# 4069_fuzz_pedal.net
KiCad netlist of a schematic drawn in EAGLE
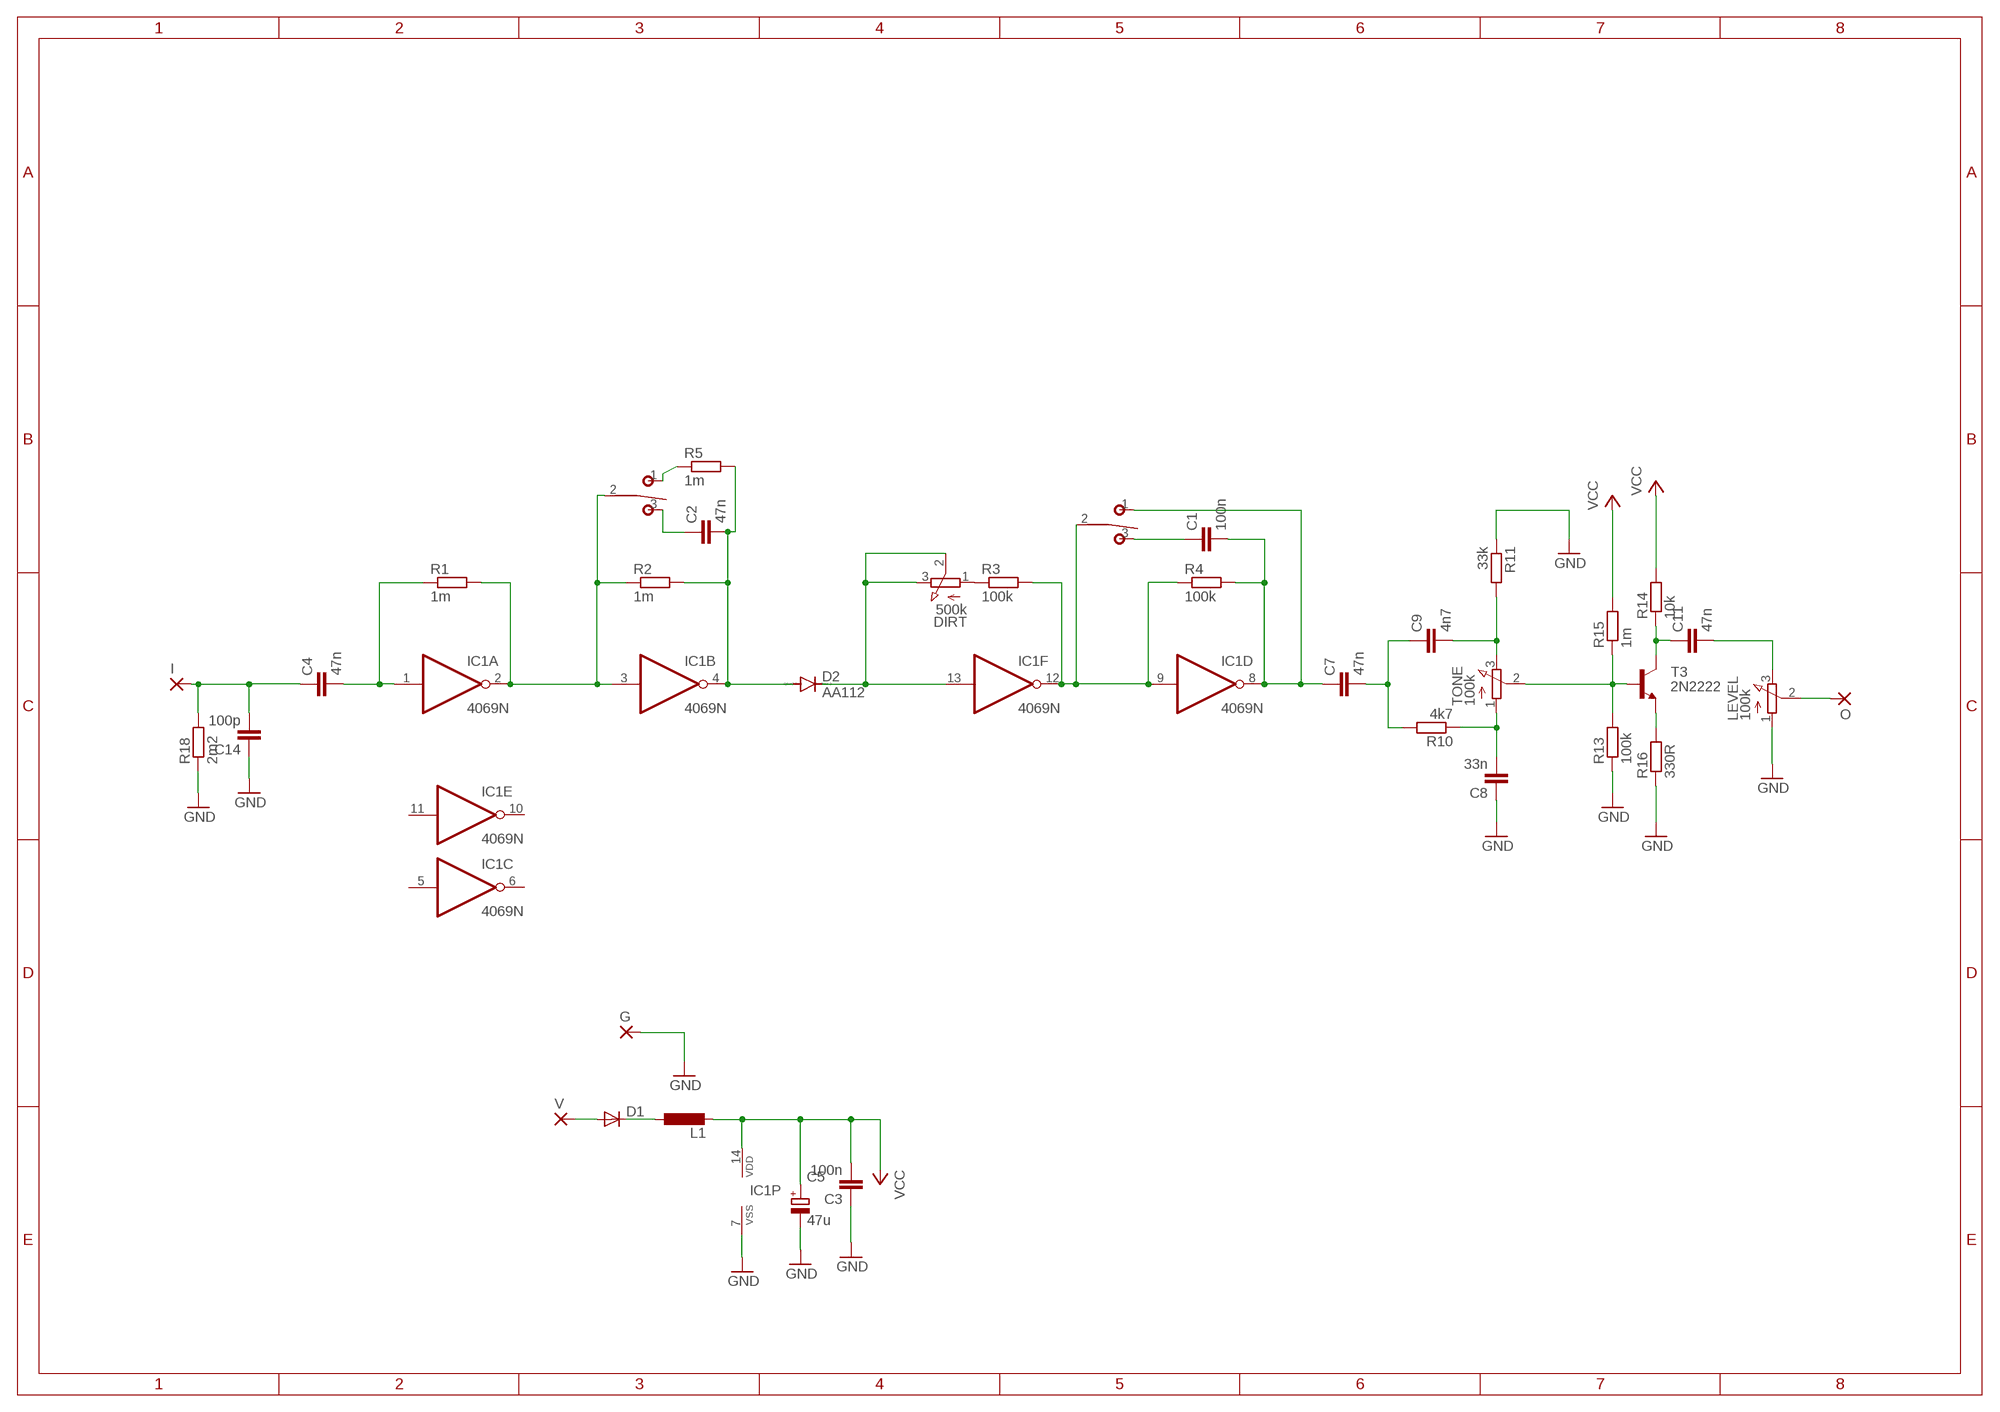
[diagram p0: schematic, sheet 1]

(export (version "E")
  (design (tool "Eeschema 10.0.6"))
  (components
    (comp (ref "C1")
      (value "100n")
      (footprint "eagle-import:C5B2.5")
      (libsource (lib "eagle-import") (part "C5/2.5"))
    )
    (comp (ref "C2")
      (value "47n")
      (footprint "eagle-import:C5B2.5")
      (libsource (lib "eagle-import") (part "C5/2.5"))
    )
    (comp (ref "C3")
      (value "100n")
      (footprint "eagle-import:C5B2.5")
      (libsource (lib "eagle-import") (part "C5/2.5"))
    )
    (comp (ref "C4")
      (value "47n")
      (footprint "eagle-import:C5B2.5")
      (libsource (lib "eagle-import") (part "C5/2.5"))
    )
    (comp (ref "C5")
      (value "47u")
      (footprint "eagle-import:E2-4")
      (libsource (lib "eagle-import") (part "CPOL-EUE2-4"))
    )
    (comp (ref "C7")
      (value "47n")
      (footprint "eagle-import:C5B2.5")
      (libsource (lib "eagle-import") (part "C5/2.5"))
    )
    (comp (ref "C8")
      (value "33n")
      (footprint "eagle-import:C5B2.5")
      (libsource (lib "eagle-import") (part "C5/2.5"))
    )
    (comp (ref "C9")
      (value "4n7")
      (footprint "eagle-import:C5B2.5")
      (libsource (lib "eagle-import") (part "C5/2.5"))
    )
    (comp (ref "C11")
      (value "47n")
      (footprint "eagle-import:C5B2.5")
      (libsource (lib "eagle-import") (part "C5/2.5"))
    )
    (comp (ref "C14")
      (value "100p")
      (footprint "eagle-import:C5B2.5")
      (libsource (lib "eagle-import") (part "C5/2.5"))
    )
    (comp (ref "D1")
      (value "SMALL_DIODEDO35-7")
      (footprint "eagle-import:DO35-7")
      (libsource (lib "eagle-import") (part "SMALL_DIODEDO35-7"))
    )
    (comp (ref "D2")
      (value "AA112")
      (footprint "eagle-import:DO07")
      (libsource (lib "eagle-import") (part "AA112"))
    )
    (comp (ref "DIRT")
      (value "500k")
      (footprint "eagle-import:3RP_1610N")
      (libsource (lib "eagle-import") (part "HEXPOT1"))
    )
    (comp (ref "G")
      (value "2,15/1,0")
      (footprint "eagle-import:2,15_1,0")
      (libsource (lib "eagle-import") (part "2,15/1,0"))
    )
    (comp (ref "I")
      (value "2,15/1,0")
      (footprint "eagle-import:2,15_1,0")
      (libsource (lib "eagle-import") (part "2,15/1,0"))
    )
    (comp (ref "IC1")
      (value "4069N")
      (footprint "eagle-import:DIL14")
      (libsource (lib "eagle-import") (part "4069N"))
    )
    (comp (ref "L1")
      (value "L-EU0204/7")
      (footprint "eagle-import:0204_7")
      (libsource (lib "eagle-import") (part "L-EU0204/7"))
    )
    (comp (ref "LEVEL")
      (value "100k")
      (footprint "eagle-import:3RP_1610N")
      (libsource (lib "eagle-import") (part "HEXPOT1"))
    )
    (comp (ref "O")
      (value "2,15/1,0")
      (footprint "eagle-import:2,15_1,0")
      (libsource (lib "eagle-import") (part "2,15/1,0"))
    )
    (comp (ref "R1")
      (value "1m")
      (footprint "eagle-import:0207_7")
      (libsource (lib "eagle-import") (part "R-EU_0207/7"))
    )
    (comp (ref "R2")
      (value "1m")
      (footprint "eagle-import:0207_7")
      (libsource (lib "eagle-import") (part "R-EU_0207/7"))
    )
    (comp (ref "R3")
      (value "100k")
      (footprint "eagle-import:0207_7")
      (libsource (lib "eagle-import") (part "R-EU_0207/7"))
    )
    (comp (ref "R4")
      (value "100k")
      (footprint "eagle-import:0207_7")
      (libsource (lib "eagle-import") (part "R-EU_0207/7"))
    )
    (comp (ref "R5")
      (value "1m")
      (footprint "eagle-import:0207_7")
      (libsource (lib "eagle-import") (part "R-EU_0207/7"))
    )
    (comp (ref "R10")
      (value "4k7")
      (footprint "eagle-import:0207_7")
      (libsource (lib "eagle-import") (part "R-EU_0207/7"))
    )
    (comp (ref "R11")
      (value "33k")
      (footprint "eagle-import:0207_7")
      (libsource (lib "eagle-import") (part "R-EU_0207/7"))
    )
    (comp (ref "R13")
      (value "100k")
      (footprint "eagle-import:0207_7")
      (libsource (lib "eagle-import") (part "R-EU_0207/7"))
    )
    (comp (ref "R14")
      (value "10k")
      (footprint "eagle-import:0207_7")
      (libsource (lib "eagle-import") (part "R-EU_0207/7"))
    )
    (comp (ref "R15")
      (value "1m")
      (footprint "eagle-import:0207_7")
      (libsource (lib "eagle-import") (part "R-EU_0207/7"))
    )
    (comp (ref "R16")
      (value "330R")
      (footprint "eagle-import:0207_7")
      (libsource (lib "eagle-import") (part "R-EU_0207/7"))
    )
    (comp (ref "R18")
      (value "2m2")
      (footprint "eagle-import:0207_7")
      (libsource (lib "eagle-import") (part "R-EU_0207/7"))
    )
    (comp (ref "T3")
      (value "2N2222")
      (footprint "eagle-import:TO18")
      (libsource (lib "eagle-import") (part "2N2222"))
    )
    (comp (ref "TONE")
      (value "100k")
      (footprint "eagle-import:3RP_1610N")
      (libsource (lib "eagle-import") (part "HEXPOT1"))
    )
    (comp (ref "U$1")
      (value "T-80-T-SPDT-ON-OFF-ON")
      (footprint "eagle-import:M9040P")
      (libsource (lib "eagle-import") (part "T-80-T-SPDT-ON-OFF-ON"))
    )
    (comp (ref "U$2")
      (value "T-80-T-SPDT-ON-OFF-ON")
      (footprint "eagle-import:M9040P")
      (libsource (lib "eagle-import") (part "T-80-T-SPDT-ON-OFF-ON"))
    )
    (comp (ref "V")
      (value "2,15/1,0")
      (footprint "eagle-import:2,15_1,0")
      (libsource (lib "eagle-import") (part "2,15/1,0"))
    )
  )
  (nets
    (net (code "1") (name "GND") (class "Default")
      (node (ref "C14") (pin "1") (pinfunction "1_1") (pintype "passive"))
      (node (ref "C3") (pin "1") (pinfunction "1_1") (pintype "passive"))
      (node (ref "C5") (pin "-") (pinfunction "-_-") (pintype "passive"))
      (node (ref "C8") (pin "1") (pinfunction "1_1") (pintype "passive"))
      (node (ref "G") (pin "1") (pinfunction "P_1") (pintype "passive"))
      (node (ref "IC1") (pin "7") (pinfunction "VSS_7") (pintype "power_in"))
      (node (ref "LEVEL") (pin "1") (pinfunction "A_1") (pintype "passive"))
      (node (ref "R11") (pin "1") (pinfunction "1_1") (pintype "passive"))
      (node (ref "R13") (pin "1") (pinfunction "1_1") (pintype "passive"))
      (node (ref "R16") (pin "1") (pinfunction "1_1") (pintype "passive"))
      (node (ref "R18") (pin "1") (pinfunction "1_1") (pintype "passive"))
    )
    (net (code "2") (name "Net-(C7-Pad2)") (class "Default")
      (node (ref "C7") (pin "2") (pinfunction "2_2") (pintype "passive"))
      (node (ref "C9") (pin "1") (pinfunction "1_1") (pintype "passive"))
      (node (ref "R10") (pin "2") (pinfunction "2_2") (pintype "passive"))
    )
    (net (code "3") (name "Net-(D1-PadC)") (class "Default")
      (node (ref "D1") (pin "C") (pinfunction "C_C") (pintype "passive"))
      (node (ref "L1") (pin "1") (pinfunction "1_1") (pintype "passive"))
    )
    (net (code "4") (name "Net-(DIRT-A)") (class "Default")
      (node (ref "DIRT") (pin "1") (pinfunction "A_1") (pintype "passive"))
      (node (ref "R3") (pin "1") (pinfunction "1_1") (pintype "passive"))
    )
    (net (code "5") (name "Net-(DIRT-E)") (class "Default")
      (node (ref "D2") (pin "C") (pinfunction "C_C") (pintype "passive"))
      (node (ref "DIRT") (pin "2") (pinfunction "S_2") (pintype "passive"))
      (node (ref "DIRT") (pin "3") (pinfunction "E_3") (pintype "passive"))
      (node (ref "IC1") (pin "13") (pinfunction "I_13") (pintype "input"))
    )
    (net (code "6") (name "Net-(I-P)") (class "Default")
      (node (ref "C14") (pin "2") (pinfunction "2_2") (pintype "passive"))
      (node (ref "C4") (pin "1") (pinfunction "1_1") (pintype "passive"))
      (node (ref "I") (pin "1") (pinfunction "P_1") (pintype "passive"))
      (node (ref "R18") (pin "2") (pinfunction "2_2") (pintype "passive"))
    )
    (net (code "7") (name "Net-(IC1A-I)") (class "Default")
      (node (ref "C4") (pin "2") (pinfunction "2_2") (pintype "passive"))
      (node (ref "IC1") (pin "1") (pinfunction "I_1") (pintype "input"))
      (node (ref "R1") (pin "1") (pinfunction "1_1") (pintype "passive"))
    )
    (net (code "8") (name "Net-(IC1A-O)") (class "Default")
      (node (ref "IC1") (pin "2") (pinfunction "O_2") (pintype "output"))
      (node (ref "IC1") (pin "3") (pinfunction "I_3") (pintype "input"))
      (node (ref "R1") (pin "2") (pinfunction "2_2") (pintype "passive"))
      (node (ref "R2") (pin "1") (pinfunction "1_1") (pintype "passive"))
      (node (ref "U$2") (pin "2") (pinfunction "P_2") (pintype "passive"))
    )
    (net (code "9") (name "Net-(IC1B-O)") (class "Default")
      (node (ref "C2") (pin "2") (pinfunction "2_2") (pintype "passive"))
      (node (ref "D2") (pin "A") (pinfunction "A_A") (pintype "passive"))
      (node (ref "IC1") (pin "4") (pinfunction "O_4") (pintype "output"))
      (node (ref "R2") (pin "2") (pinfunction "2_2") (pintype "passive"))
      (node (ref "R5") (pin "2") (pinfunction "2_2") (pintype "passive"))
    )
    (net (code "10") (name "Net-(IC1D-I)") (class "Default")
      (node (ref "IC1") (pin "12") (pinfunction "O_12") (pintype "output"))
      (node (ref "IC1") (pin "9") (pinfunction "I_9") (pintype "input"))
      (node (ref "R3") (pin "2") (pinfunction "2_2") (pintype "passive"))
      (node (ref "R4") (pin "1") (pinfunction "1_1") (pintype "passive"))
      (node (ref "U$1") (pin "2") (pinfunction "P_2") (pintype "passive"))
    )
    (net (code "11") (name "Net-(IC1D-O)") (class "Default")
      (node (ref "C1") (pin "2") (pinfunction "2_2") (pintype "passive"))
      (node (ref "C7") (pin "1") (pinfunction "1_1") (pintype "passive"))
      (node (ref "IC1") (pin "8") (pinfunction "O_8") (pintype "output"))
      (node (ref "R4") (pin "2") (pinfunction "2_2") (pintype "passive"))
      (node (ref "U$1") (pin "1") (pinfunction "O_1") (pintype "passive"))
    )
    (net (code "12") (name "Net-(LEVEL-E)") (class "Default")
      (node (ref "C11") (pin "2") (pinfunction "2_2") (pintype "passive"))
      (node (ref "LEVEL") (pin "3") (pinfunction "E_3") (pintype "passive"))
    )
    (net (code "13") (name "Net-(LEVEL-S)") (class "Default")
      (node (ref "LEVEL") (pin "2") (pinfunction "S_2") (pintype "passive"))
      (node (ref "O") (pin "1") (pinfunction "P_1") (pintype "passive"))
    )
    (net (code "14") (name "Net-(T3-B)") (class "Default")
      (node (ref "R13") (pin "2") (pinfunction "2_2") (pintype "passive"))
      (node (ref "R15") (pin "1") (pinfunction "1_1") (pintype "passive"))
      (node (ref "T3") (pin "2") (pinfunction "B_2") (pintype "passive"))
      (node (ref "TONE") (pin "2") (pinfunction "S_2") (pintype "passive"))
    )
    (net (code "15") (name "Net-(T3-C)") (class "Default")
      (node (ref "C11") (pin "1") (pinfunction "1_1") (pintype "passive"))
      (node (ref "R14") (pin "1") (pinfunction "1_1") (pintype "passive"))
      (node (ref "T3") (pin "3") (pinfunction "C_3") (pintype "passive"))
    )
    (net (code "16") (name "Net-(T3-E)") (class "Default")
      (node (ref "R16") (pin "2") (pinfunction "2_2") (pintype "passive"))
      (node (ref "T3") (pin "1") (pinfunction "E_1") (pintype "passive"))
    )
    (net (code "17") (name "Net-(TONE-A)") (class "Default")
      (node (ref "C8") (pin "2") (pinfunction "2_2") (pintype "passive"))
      (node (ref "R10") (pin "1") (pinfunction "1_1") (pintype "passive"))
      (node (ref "TONE") (pin "1") (pinfunction "A_1") (pintype "passive"))
    )
    (net (code "18") (name "Net-(TONE-E)") (class "Default")
      (node (ref "C9") (pin "2") (pinfunction "2_2") (pintype "passive"))
      (node (ref "R11") (pin "2") (pinfunction "2_2") (pintype "passive"))
      (node (ref "TONE") (pin "3") (pinfunction "E_3") (pintype "passive"))
    )
    (net (code "19") (name "Net-(U$1-S)") (class "Default")
      (node (ref "C1") (pin "1") (pinfunction "1_1") (pintype "passive"))
      (node (ref "U$1") (pin "3") (pinfunction "S_3") (pintype "passive"))
    )
    (net (code "20") (name "Net-(U$2-O)") (class "Default")
      (node (ref "R5") (pin "1") (pinfunction "1_1") (pintype "passive"))
      (node (ref "U$2") (pin "1") (pinfunction "O_1") (pintype "passive"))
    )
    (net (code "21") (name "Net-(U$2-S)") (class "Default")
      (node (ref "C2") (pin "1") (pinfunction "1_1") (pintype "passive"))
      (node (ref "U$2") (pin "3") (pinfunction "S_3") (pintype "passive"))
    )
    (net (code "22") (name "Net-(V-P)") (class "Default")
      (node (ref "D1") (pin "A") (pinfunction "A_A") (pintype "passive"))
      (node (ref "V") (pin "1") (pinfunction "P_1") (pintype "passive"))
    )
    (net (code "23") (name "VCC") (class "Default")
      (node (ref "C3") (pin "2") (pinfunction "2_2") (pintype "passive"))
      (node (ref "C5") (pin "+") (pinfunction "+_+") (pintype "passive"))
      (node (ref "IC1") (pin "14") (pinfunction "VDD_14") (pintype "power_in"))
      (node (ref "L1") (pin "2") (pinfunction "2_2") (pintype "passive"))
      (node (ref "R14") (pin "2") (pinfunction "2_2") (pintype "passive"))
      (node (ref "R15") (pin "2") (pinfunction "2_2") (pintype "passive"))
    )
    (net (code "24") (name "unconnected-(IC1C-I-Pad5)") (class "Default")
      (node (ref "IC1") (pin "5") (pinfunction "I_5") (pintype "input"))
    )
    (net (code "25") (name "unconnected-(IC1C-O-Pad6)") (class "Default")
      (node (ref "IC1") (pin "6") (pinfunction "O_6") (pintype "output"))
    )
    (net (code "26") (name "unconnected-(IC1E-I-Pad11)") (class "Default")
      (node (ref "IC1") (pin "11") (pinfunction "I_11") (pintype "input"))
    )
    (net (code "27") (name "unconnected-(IC1E-O-Pad10)") (class "Default")
      (node (ref "IC1") (pin "10") (pinfunction "O_10") (pintype "output"))
    )
  )
)
